# 05_UFS.net
KiCad netlist of a schematic drawn in Altium Designer
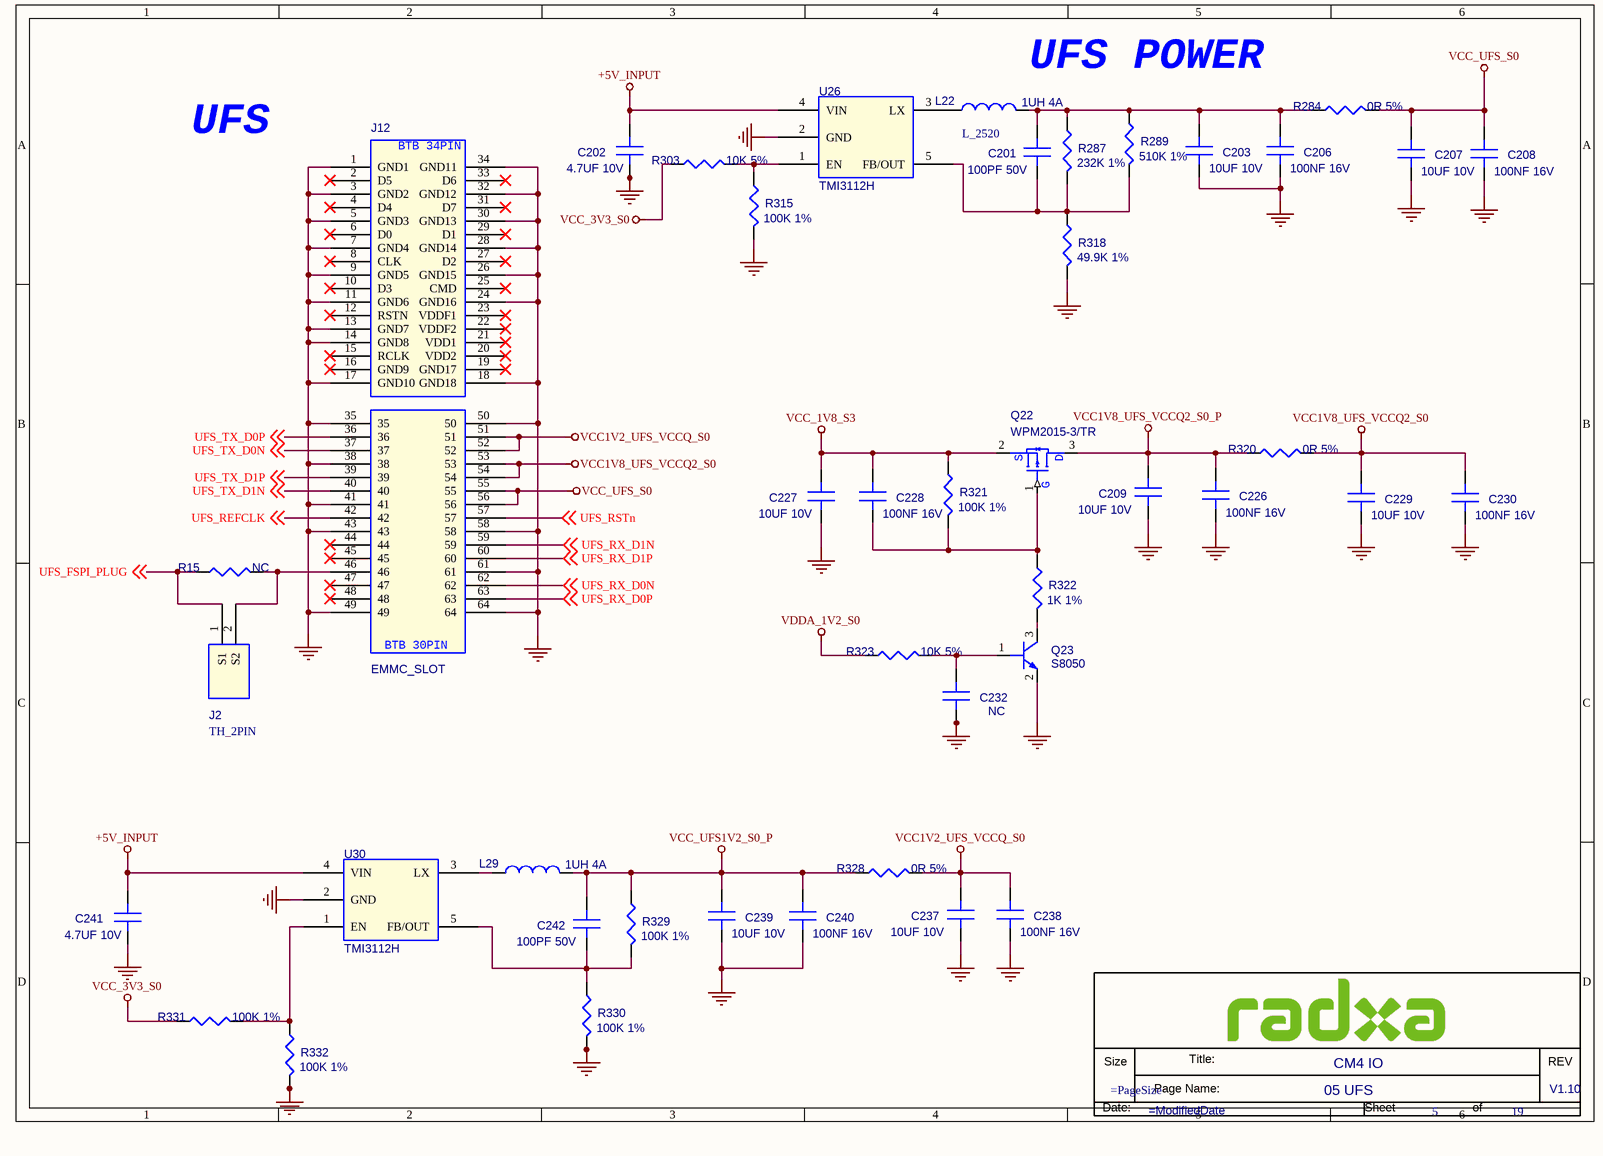
[diagram p0: 05 UFS.SchDoc]

(export (version "E")
  (design (tool "Eeschema 10.0.6"))
  (components
    (comp (ref "C201")
      (value "100PF 50V")
      (footprint "C0201")
      (description "SMD  0201  100PF  50V  X5R  ±5%  ROHS")
      (fields (field (name "PART NUMBER") "A1C01.00070"))
      (libsource (lib "*") (part "C"))
    )
    (comp (ref "C202")
      (value "4.7UF 10V")
      (footprint "C0402")
      (description "SMD  0402  4.7UF  10V  X5R  ±20%  ROHS")
      (fields (field (name "PART NUMBER") "A1C01.00073"))
      (libsource (lib "*") (part "C"))
    )
    (comp (ref "C203")
      (value "10UF 10V")
      (footprint "C0402")
      (description "SMD  0402  10UF  10V  X5R  ±20%  ROHS")
      (fields (field (name "PART NUMBER") "A1C01.00025"))
      (libsource (lib "*") (part "C"))
    )
    (comp (ref "C206")
      (value "100NF 16V")
      (footprint "C0201")
      (description "SMD  0201  100NF  16V  X5R  ±20%  ROHS")
      (fields (field (name "PART NUMBER") "A1C01.00099"))
      (libsource (lib "*") (part "C"))
    )
    (comp (ref "C207")
      (value "10UF 10V")
      (footprint "C0402")
      (description "SMD  0402  10UF  10V  X5R  ±20%  ROHS")
      (fields (field (name "PART NUMBER") "A1C01.00025"))
      (libsource (lib "*") (part "C"))
    )
    (comp (ref "C208")
      (value "100NF 16V")
      (footprint "C0201")
      (description "SMD  0201  100NF  16V  X5R  ±20%  ROHS")
      (fields (field (name "PART NUMBER") "A1C01.00099"))
      (libsource (lib "*") (part "C"))
    )
    (comp (ref "C209")
      (value "10UF 10V")
      (footprint "C0402")
      (description "SMD  0402  10UF  10V  X5R  ±20%  ROHS")
      (fields (field (name "PART NUMBER") "A1C01.00025"))
      (libsource (lib "*") (part "C"))
    )
    (comp (ref "C226")
      (value "100NF 16V")
      (footprint "C0201")
      (description "SMD  0201  100NF  16V  X5R  ±20%  ROHS")
      (fields (field (name "PART NUMBER") "A1C01.00099"))
      (libsource (lib "*") (part "C"))
    )
    (comp (ref "C227")
      (value "10UF 10V")
      (footprint "C0402")
      (description "SMD  0402  10UF  10V  X5R  ±20%  ROHS")
      (fields (field (name "PART NUMBER") "A1C01.00025"))
      (libsource (lib "*") (part "C"))
    )
    (comp (ref "C228")
      (value "100NF 16V")
      (footprint "C0201")
      (description "SMD  0201  100NF  16V  X5R  ±20%  ROHS")
      (fields (field (name "PART NUMBER") "A1C01.00099"))
      (libsource (lib "*") (part "C"))
    )
    (comp (ref "C229")
      (value "10UF 10V")
      (footprint "C0402")
      (description "SMD  0402  10UF  10V  X5R  ±20%  ROHS")
      (fields (field (name "PART NUMBER") "A1C01.00025"))
      (libsource (lib "*") (part "C"))
    )
    (comp (ref "C230")
      (value "100NF 16V")
      (footprint "C0201")
      (description "SMD  0201  100NF  16V  X5R  ±20%  ROHS")
      (fields (field (name "PART NUMBER") "A1C01.00099"))
      (libsource (lib "*") (part "C"))
    )
    (comp (ref "C232")
      (value "NC")
      (footprint "C0201")
      (description "SMD  0201  100NF  10V  X5R  ±20%  ROHS")
      (fields (field (name "PART NUMBER") "A1C01.00009"))
      (libsource (lib "*") (part "C"))
    )
    (comp (ref "C237")
      (value "10UF 10V")
      (footprint "C0402")
      (description "SMD  0402  10UF  10V  X5R  ±20%  ROHS")
      (fields (field (name "PART NUMBER") "A1C01.00025"))
      (libsource (lib "*") (part "C"))
    )
    (comp (ref "C238")
      (value "100NF 16V")
      (footprint "C0201")
      (description "SMD  0201  100NF  16V  X5R  ±20%  ROHS")
      (fields (field (name "PART NUMBER") "A1C01.00099"))
      (libsource (lib "*") (part "C"))
    )
    (comp (ref "C239")
      (value "10UF 10V")
      (footprint "C0402")
      (description "SMD  0402  10UF  10V  X5R  ±20%  ROHS")
      (fields (field (name "PART NUMBER") "A1C01.00025"))
      (libsource (lib "*") (part "C"))
    )
    (comp (ref "C240")
      (value "100NF 16V")
      (footprint "C0201")
      (description "SMD  0201  100NF  16V  X5R  ±20%  ROHS")
      (fields (field (name "PART NUMBER") "A1C01.00099"))
      (libsource (lib "*") (part "C"))
    )
    (comp (ref "C241")
      (value "4.7UF 10V")
      (footprint "C0402")
      (description "SMD  0402  4.7UF  10V  X5R  ±20%  ROHS")
      (fields (field (name "PART NUMBER") "A1C01.00073"))
      (libsource (lib "*") (part "C"))
    )
    (comp (ref "C242")
      (value "100PF 50V")
      (footprint "C0201")
      (description "SMD  0201  100PF  50V  X5R  ±5%  ROHS")
      (fields (field (name "PART NUMBER") "A1C01.00070"))
      (libsource (lib "*") (part "C"))
    )
    (comp (ref "J2")
      (value "TH_2PIN")
      (footprint "CON_TH1X2_2D54_STA")
      (fields (field (name "PART NUMBER") "A1J02.00011"))
      (libsource (lib "*") (part "TH_2PIN"))
    )
    (comp (ref "J12")
      (value "EMMC_SLOT")
      (footprint "EMMC_SLOT_30P_34P")
      (description "SMD  公座  2*17PIN  180度  8.3*2.7  0.4mm脚距  GB042-34P-H10-E3000  黑色  LG  ROHS")
      (fields (field (name "PART NUMBER") "A1J01.00030"))
      (libsource (lib "*") (part "EMMC_SLOT"))
    )
    (comp (ref "L22")
      (value "1UH 4A")
      (footprint "L_2520")
      (description "SMD  带屏蔽  2.5x2x1.2mm  1UH  4A  ±20%  RHP252012T-1R0MT  仁芯微  ROHS")
      (fields (field (name "PCB FOOTPRINT") "L_2520") (field (name "PART NUMBER") "A1L01.00117"))
      (libsource (lib "*") (part "L"))
    )
    (comp (ref "L29")
      (value "1UH 4A")
      (footprint "L_2520")
      (description "SMD  带屏蔽  2.5x2x1.2mm  1UH  4A  ±20%  RHP252012T-1R0MT  仁芯微  ROHS")
      (fields (field (name "PART NUMBER") "A1L01.00117"))
      (libsource (lib "*") (part "L"))
    )
    (comp (ref "Q22")
      (value "WPM2015-3/TR")
      (footprint "SOT_23")
      (description "SMD编带  SOT-23  WPM2015-3/TR  P沟道  ROHS")
      (fields (field (name "PART NUMBER") "A1D01.00019"))
      (libsource (lib "*") (part "MOSFET_PNP"))
    )
    (comp (ref "Q23")
      (value "S8050")
      (footprint "SOT_23")
      (description "SMD编带  SOT-23  S8050  NPN  ROHS")
      (fields
        (field (name "MANUFACTURER") "长电")
        (field (name "PART NUMBER") "A1D01.00009")
        (field (name "CREATED BY") "JJJ")
      )
      (libsource (lib "*") (part "NPN"))
    )
    (comp (ref "R15")
      (value "NC")
      (footprint "R0402")
      (description "SMD  0201  0R  1/20W  ±5%  ROHS")
      (fields (field (name "PART NUMBER") "A1R01.00027"))
      (libsource (lib "*") (part "R"))
    )
    (comp (ref "R284")
      (value "0R 5%")
      (footprint "R0402")
      (description "SMD  0201  0R  1/20W  ±5%  ROHS")
      (fields (field (name "PART NUMBER") "A1R01.00027"))
      (libsource (lib "*") (part "R"))
    )
    (comp (ref "R287")
      (value "232K 1%")
      (footprint "R0402")
      (description "SMD  0201  232K  1/20W  ±1%  ROHS")
      (fields (field (name "PART NUMBER") "A1R01.00189"))
      (libsource (lib "*") (part "R"))
    )
    (comp (ref "R289")
      (value "510K 1%")
      (footprint "R0402")
      (description "SMD  0201  510K  1/20W  ±1%  ROHS")
      (fields (field (name "PART NUMBER") "A1R01.00460"))
      (libsource (lib "*") (part "R"))
    )
    (comp (ref "R303")
      (value "10K 5%")
      (footprint "R0402")
      (description "SMD  0201  10K  1/20W  ±5%  ROHS")
      (fields (field (name "PART NUMBER") "A1R01.00012"))
      (libsource (lib "*") (part "R"))
    )
    (comp (ref "R315")
      (value "100K 1%")
      (footprint "R0402")
      (description "SMD  0201  100K  1/20W  ±1%  ROHS")
      (fields (field (name "PART NUMBER") "A1R01.00165"))
      (libsource (lib "*") (part "R"))
    )
    (comp (ref "R318")
      (value "49.9K 1%")
      (footprint "R0402")
      (description "SMD  0201  49.9K  1/20W  ±1%  ROHS")
      (fields (field (name "PART NUMBER") "A1R01.00207"))
      (libsource (lib "*") (part "R"))
    )
    (comp (ref "R320")
      (value "0R 5%")
      (footprint "R0402")
      (description "SMD  0201  0R  1/20W  ±5%  ROHS")
      (fields (field (name "PART NUMBER") "A1R01.00027"))
      (libsource (lib "*") (part "R"))
    )
    (comp (ref "R321")
      (value "100K 1%")
      (footprint "R0402")
      (description "SMD  0201  100K  1/20W  ±1%  ROHS")
      (fields (field (name "PART NUMBER") "A1R01.00165"))
      (libsource (lib "*") (part "R"))
    )
    (comp (ref "R322")
      (value "1K 1%")
      (footprint "R0402")
      (description "SMD  0201  1K  1/20W  ±1%  ROHS")
      (fields (field (name "PART NUMBER") "A1R01.00111"))
      (libsource (lib "*") (part "R"))
    )
    (comp (ref "R323")
      (value "10K 5%")
      (footprint "R0402")
      (description "SMD  0201  10K  1/20W  ±5%  ROHS")
      (fields (field (name "PART NUMBER") "A1R01.00012"))
      (libsource (lib "*") (part "R"))
    )
    (comp (ref "R328")
      (value "0R 5%")
      (footprint "R0402")
      (description "SMD  0201  0R  1/20W  ±5%  ROHS")
      (fields (field (name "PART NUMBER") "A1R01.00027"))
      (libsource (lib "*") (part "R"))
    )
    (comp (ref "R329")
      (value "100K 1%")
      (footprint "R0402")
      (description "SMD  0201  100K  1/20W  ±1%  ROHS")
      (fields (field (name "PART NUMBER") "A1R01.00165"))
      (libsource (lib "*") (part "R"))
    )
    (comp (ref "R330")
      (value "100K 1%")
      (footprint "R0402")
      (description "SMD  0201  100K  1/20W  ±1%  ROHS")
      (fields (field (name "PART NUMBER") "A1R01.00165"))
      (libsource (lib "*") (part "R"))
    )
    (comp (ref "R331")
      (value "100K 1%")
      (footprint "R0402")
      (description "SMD  0201  100K  1/20W  ±1%  ROHS")
      (fields (field (name "PART NUMBER") "A1R01.00165"))
      (libsource (lib "*") (part "R"))
    )
    (comp (ref "R332")
      (value "100K 1%")
      (footprint "R0402")
      (description "SMD  0201  100K  1/20W  ±1%  ROHS")
      (fields (field (name "PART NUMBER") "A1R01.00165"))
      (libsource (lib "*") (part "R"))
    )
    (comp (ref "U26")
      (value "TMI3112H")
      (footprint "SOT23_5")
      (description "SMD  降压转换器  TMI3112H  SOT-23-5  TMI  ROHS")
      (fields
        (field (name "PART NUMBER") "A1I01.00618")
        (field (name "MANUFACTURER") "TMI(拓尔微电子)")
        (field (name "CREATED BY") "JJJ")
      )
      (libsource (lib "*") (part "DCDC_ETA3409"))
    )
    (comp (ref "U30")
      (value "TMI3112H")
      (footprint "SOT23_5")
      (description "SMD  降压转换器  TMI3112H  SOT-23-5  TMI  ROHS")
      (fields
        (field (name "MANUFACTURER") "TMI(拓尔微电子)")
        (field (name "PART NUMBER") "A1I01.00618")
        (field (name "CREATED BY") "JJJ")
      )
      (libsource (lib "*") (part "DCDC_ETA3409"))
    )
  )
  (nets
    (net (code "1") (name "+5V_INPUT") (class "Default")
      (node (ref "C202") (pin "1") (pinfunction "A_1") (pintype "passive"))
      (node (ref "C241") (pin "1") (pinfunction "A_1") (pintype "passive"))
      (node (ref "U26") (pin "4") (pinfunction "VIN_4") (pintype "passive"))
      (node (ref "U30") (pin "4") (pinfunction "VIN_4") (pintype "passive"))
    )
    (net (code "2") (name "GND") (class "Default")
      (node (ref "C202") (pin "2") (pinfunction "B_2") (pintype "passive"))
      (node (ref "C203") (pin "2") (pinfunction "B_2") (pintype "passive"))
      (node (ref "C206") (pin "2") (pinfunction "B_2") (pintype "passive"))
      (node (ref "C207") (pin "2") (pinfunction "B_2") (pintype "passive"))
      (node (ref "C208") (pin "2") (pinfunction "B_2") (pintype "passive"))
      (node (ref "C209") (pin "2") (pinfunction "B_2") (pintype "passive"))
      (node (ref "C226") (pin "2") (pinfunction "B_2") (pintype "passive"))
      (node (ref "C227") (pin "2") (pinfunction "B_2") (pintype "passive"))
      (node (ref "C229") (pin "2") (pinfunction "B_2") (pintype "passive"))
      (node (ref "C230") (pin "2") (pinfunction "B_2") (pintype "passive"))
      (node (ref "C232") (pin "2") (pinfunction "B_2") (pintype "passive"))
      (node (ref "C237") (pin "2") (pinfunction "B_2") (pintype "passive"))
      (node (ref "C238") (pin "2") (pinfunction "B_2") (pintype "passive"))
      (node (ref "C239") (pin "2") (pinfunction "B_2") (pintype "passive"))
      (node (ref "C240") (pin "2") (pinfunction "B_2") (pintype "passive"))
      (node (ref "C241") (pin "2") (pinfunction "B_2") (pintype "passive"))
      (node (ref "J12") (pin "1") (pinfunction "GND1_1") (pintype "passive"))
      (node (ref "J12") (pin "11") (pinfunction "GND6_11") (pintype "passive"))
      (node (ref "J12") (pin "13") (pinfunction "GND7_13") (pintype "passive"))
      (node (ref "J12") (pin "14") (pinfunction "GND8_14") (pintype "passive"))
      (node (ref "J12") (pin "17") (pinfunction "GND10_17") (pintype "passive"))
      (node (ref "J12") (pin "18") (pinfunction "GND18_18") (pintype "passive"))
      (node (ref "J12") (pin "24") (pinfunction "GND16_24") (pintype "passive"))
      (node (ref "J12") (pin "26") (pinfunction "GND15_26") (pintype "passive"))
      (node (ref "J12") (pin "28") (pinfunction "GND14_28") (pintype "passive"))
      (node (ref "J12") (pin "3") (pinfunction "GND2_3") (pintype "passive"))
      (node (ref "J12") (pin "30") (pinfunction "GND13_30") (pintype "passive"))
      (node (ref "J12") (pin "32") (pinfunction "GND12_32") (pintype "passive"))
      (node (ref "J12") (pin "34") (pinfunction "GND11_34") (pintype "passive"))
      (node (ref "J12") (pin "35") (pinfunction "35_35") (pintype "passive"))
      (node (ref "J12") (pin "38") (pinfunction "38_38") (pintype "passive"))
      (node (ref "J12") (pin "41") (pinfunction "41_41") (pintype "passive"))
      (node (ref "J12") (pin "43") (pinfunction "43_43") (pintype "passive"))
      (node (ref "J12") (pin "49") (pinfunction "49_49") (pintype "passive"))
      (node (ref "J12") (pin "5") (pinfunction "GND3_5") (pintype "passive"))
      (node (ref "J12") (pin "50") (pinfunction "50_50") (pintype "passive"))
      (node (ref "J12") (pin "58") (pinfunction "58_58") (pintype "passive"))
      (node (ref "J12") (pin "61") (pinfunction "61_61") (pintype "passive"))
      (node (ref "J12") (pin "64") (pinfunction "64_64") (pintype "passive"))
      (node (ref "J12") (pin "7") (pinfunction "GND4_7") (pintype "passive"))
      (node (ref "J12") (pin "9") (pinfunction "GND5_9") (pintype "passive"))
      (node (ref "Q23") (pin "2") (pinfunction "EMITTER_2") (pintype "passive"))
      (node (ref "R315") (pin "2") (pinfunction "2_2") (pintype "passive"))
      (node (ref "R318") (pin "2") (pinfunction "2_2") (pintype "passive"))
      (node (ref "R330") (pin "2") (pinfunction "2_2") (pintype "passive"))
      (node (ref "R332") (pin "2") (pinfunction "2_2") (pintype "passive"))
      (node (ref "U26") (pin "2") (pinfunction "GND_2") (pintype "passive"))
      (node (ref "U30") (pin "2") (pinfunction "GND_2") (pintype "passive"))
    )
    (net (code "3") (name "Net-(C201-A)") (class "Default")
      (node (ref "C201") (pin "1") (pinfunction "A_1") (pintype "passive"))
      (node (ref "C203") (pin "1") (pinfunction "A_1") (pintype "passive"))
      (node (ref "C206") (pin "1") (pinfunction "A_1") (pintype "passive"))
      (node (ref "L22") (pin "2") (pinfunction "2_2") (pintype "passive"))
      (node (ref "R284") (pin "1") (pinfunction "1_1") (pintype "passive"))
      (node (ref "R287") (pin "1") (pinfunction "1_1") (pintype "passive"))
      (node (ref "R289") (pin "1") (pinfunction "1_1") (pintype "passive"))
    )
    (net (code "4") (name "Net-(C201-B)") (class "Default")
      (node (ref "C201") (pin "2") (pinfunction "B_2") (pintype "passive"))
      (node (ref "R287") (pin "2") (pinfunction "2_2") (pintype "passive"))
      (node (ref "R289") (pin "2") (pinfunction "2_2") (pintype "passive"))
      (node (ref "R318") (pin "1") (pinfunction "1_1") (pintype "passive"))
      (node (ref "U26") (pin "5") (pinfunction "FB/OUT_5") (pintype "passive"))
    )
    (net (code "5") (name "Net-(C228-B)") (class "Default")
      (node (ref "C228") (pin "2") (pinfunction "B_2") (pintype "passive"))
      (node (ref "Q22") (pin "1") (pinfunction "G_1") (pintype "input"))
      (node (ref "R321") (pin "2") (pinfunction "2_2") (pintype "passive"))
      (node (ref "R322") (pin "1") (pinfunction "1_1") (pintype "passive"))
    )
    (net (code "6") (name "Net-(C232-A)") (class "Default")
      (node (ref "C232") (pin "1") (pinfunction "A_1") (pintype "passive"))
      (node (ref "Q23") (pin "1") (pinfunction "BASE_1") (pintype "passive"))
      (node (ref "R323") (pin "2") (pinfunction "2_2") (pintype "passive"))
    )
    (net (code "7") (name "Net-(C242-B)") (class "Default")
      (node (ref "C242") (pin "2") (pinfunction "B_2") (pintype "passive"))
      (node (ref "R329") (pin "2") (pinfunction "2_2") (pintype "passive"))
      (node (ref "R330") (pin "1") (pinfunction "1_1") (pintype "passive"))
      (node (ref "U30") (pin "5") (pinfunction "FB/OUT_5") (pintype "passive"))
    )
    (net (code "8") (name "Net-(J2-S2)") (class "Default")
      (node (ref "J12") (pin "46") (pinfunction "46_46") (pintype "passive"))
      (node (ref "J2") (pin "2") (pinfunction "S2_2") (pintype "passive"))
      (node (ref "R15") (pin "2") (pinfunction "2_2") (pintype "passive"))
    )
    (net (code "9") (name "Net-(Q23-COLLECTOR)") (class "Default")
      (node (ref "Q23") (pin "3") (pinfunction "COLLECTOR_3") (pintype "passive"))
      (node (ref "R322") (pin "2") (pinfunction "2_2") (pintype "passive"))
    )
    (net (code "10") (name "Net-(U26-EN)") (class "Default")
      (node (ref "R303") (pin "2") (pinfunction "2_2") (pintype "passive"))
      (node (ref "R315") (pin "1") (pinfunction "1_1") (pintype "passive"))
      (node (ref "U26") (pin "1") (pinfunction "EN_1") (pintype "passive"))
    )
    (net (code "11") (name "Net-(U26-LX)") (class "Default")
      (node (ref "L22") (pin "1") (pinfunction "1_1") (pintype "passive"))
      (node (ref "U26") (pin "3") (pinfunction "LX_3") (pintype "passive"))
    )
    (net (code "12") (name "Net-(U30-EN)") (class "Default")
      (node (ref "R331") (pin "2") (pinfunction "2_2") (pintype "passive"))
      (node (ref "R332") (pin "1") (pinfunction "1_1") (pintype "passive"))
      (node (ref "U30") (pin "1") (pinfunction "EN_1") (pintype "passive"))
    )
    (net (code "13") (name "Net-(U30-LX)") (class "Default")
      (node (ref "L29") (pin "1") (pinfunction "1_1") (pintype "passive"))
      (node (ref "U30") (pin "3") (pinfunction "LX_3") (pintype "passive"))
    )
    (net (code "14") (name "UFS_FSPI_PLUG") (class "Default")
      (node (ref "J2") (pin "1") (pinfunction "S1_1") (pintype "passive"))
      (node (ref "R15") (pin "1") (pinfunction "1_1") (pintype "passive"))
    )
    (net (code "15") (name "UFS_REFCLK") (class "Default")
      (node (ref "J12") (pin "42") (pinfunction "42_42") (pintype "passive"))
    )
    (net (code "16") (name "UFS_RSTn") (class "Default")
      (node (ref "J12") (pin "57") (pinfunction "57_57") (pintype "passive"))
    )
    (net (code "17") (name "UFS_RX_D0N") (class "Default")
      (node (ref "J12") (pin "62") (pinfunction "62_62") (pintype "passive"))
    )
    (net (code "18") (name "UFS_RX_D0P") (class "Default")
      (node (ref "J12") (pin "63") (pinfunction "63_63") (pintype "passive"))
    )
    (net (code "19") (name "UFS_RX_D1N") (class "Default")
      (node (ref "J12") (pin "59") (pinfunction "59_59") (pintype "passive"))
    )
    (net (code "20") (name "UFS_RX_D1P") (class "Default")
      (node (ref "J12") (pin "60") (pinfunction "60_60") (pintype "passive"))
    )
    (net (code "21") (name "UFS_TX_D0N") (class "Default")
      (node (ref "J12") (pin "37") (pinfunction "37_37") (pintype "passive"))
    )
    (net (code "22") (name "UFS_TX_D0P") (class "Default")
      (node (ref "J12") (pin "36") (pinfunction "36_36") (pintype "passive"))
    )
    (net (code "23") (name "UFS_TX_D1N") (class "Default")
      (node (ref "J12") (pin "40") (pinfunction "40_40") (pintype "passive"))
    )
    (net (code "24") (name "UFS_TX_D1P") (class "Default")
      (node (ref "J12") (pin "39") (pinfunction "39_39") (pintype "passive"))
    )
    (net (code "25") (name "VCC1V2_UFS_VCCQ_S0") (class "Default")
      (node (ref "C237") (pin "1") (pinfunction "A_1") (pintype "passive"))
      (node (ref "C238") (pin "1") (pinfunction "A_1") (pintype "passive"))
      (node (ref "J12") (pin "51") (pinfunction "51_51") (pintype "passive"))
      (node (ref "J12") (pin "52") (pinfunction "52_52") (pintype "passive"))
      (node (ref "R328") (pin "2") (pinfunction "2_2") (pintype "passive"))
    )
    (net (code "26") (name "VCC1V8_UFS_VCCQ2_S0") (class "Default")
      (node (ref "C229") (pin "1") (pinfunction "A_1") (pintype "passive"))
      (node (ref "C230") (pin "1") (pinfunction "A_1") (pintype "passive"))
      (node (ref "J12") (pin "53") (pinfunction "53_53") (pintype "passive"))
      (node (ref "J12") (pin "54") (pinfunction "54_54") (pintype "passive"))
      (node (ref "R320") (pin "2") (pinfunction "2_2") (pintype "passive"))
    )
    (net (code "27") (name "VCC1V8_UFS_VCCQ2_S0_P") (class "Default")
      (node (ref "C209") (pin "1") (pinfunction "A_1") (pintype "passive"))
      (node (ref "C226") (pin "1") (pinfunction "A_1") (pintype "passive"))
      (node (ref "Q22") (pin "3") (pinfunction "D_3") (pintype "passive"))
      (node (ref "R320") (pin "1") (pinfunction "1_1") (pintype "passive"))
    )
    (net (code "28") (name "VCC_1V8_S3") (class "Default")
      (node (ref "C227") (pin "1") (pinfunction "A_1") (pintype "passive"))
      (node (ref "C228") (pin "1") (pinfunction "A_1") (pintype "passive"))
      (node (ref "Q22") (pin "2") (pinfunction "S_2") (pintype "passive"))
      (node (ref "R321") (pin "1") (pinfunction "1_1") (pintype "passive"))
    )
    (net (code "29") (name "VCC_3V3_S0") (class "Default")
      (node (ref "R303") (pin "1") (pinfunction "1_1") (pintype "passive"))
      (node (ref "R331") (pin "1") (pinfunction "1_1") (pintype "passive"))
    )
    (net (code "30") (name "VCC_UFS1V2_S0_P") (class "Default")
      (node (ref "C239") (pin "1") (pinfunction "A_1") (pintype "passive"))
      (node (ref "C240") (pin "1") (pinfunction "A_1") (pintype "passive"))
      (node (ref "C242") (pin "1") (pinfunction "A_1") (pintype "passive"))
      (node (ref "L29") (pin "2") (pinfunction "2_2") (pintype "passive"))
      (node (ref "R328") (pin "1") (pinfunction "1_1") (pintype "passive"))
      (node (ref "R329") (pin "1") (pinfunction "1_1") (pintype "passive"))
    )
    (net (code "31") (name "VCC_UFS_S0") (class "Default")
      (node (ref "C207") (pin "1") (pinfunction "A_1") (pintype "passive"))
      (node (ref "C208") (pin "1") (pinfunction "A_1") (pintype "passive"))
      (node (ref "J12") (pin "55") (pinfunction "55_55") (pintype "passive"))
      (node (ref "J12") (pin "56") (pinfunction "56_56") (pintype "passive"))
      (node (ref "R284") (pin "2") (pinfunction "2_2") (pintype "passive"))
    )
    (net (code "32") (name "VDDA_1V2_S0") (class "Default")
      (node (ref "R323") (pin "1") (pinfunction "1_1") (pintype "passive"))
    )
    (net (code "33") (name "unconnected-(J12-CLK-Pad8)") (class "Default")
      (node (ref "J12") (pin "8") (pinfunction "CLK_8") (pintype "passive+no_connect"))
    )
    (net (code "34") (name "unconnected-(J12-CMD-Pad25)") (class "Default")
      (node (ref "J12") (pin "25") (pinfunction "CMD_25") (pintype "passive+no_connect"))
    )
    (net (code "35") (name "unconnected-(J12-D0-Pad6)") (class "Default")
      (node (ref "J12") (pin "6") (pinfunction "D0_6") (pintype "passive+no_connect"))
    )
    (net (code "36") (name "unconnected-(J12-D1-Pad29)") (class "Default")
      (node (ref "J12") (pin "29") (pinfunction "D1_29") (pintype "passive+no_connect"))
    )
    (net (code "37") (name "unconnected-(J12-D2-Pad27)") (class "Default")
      (node (ref "J12") (pin "27") (pinfunction "D2_27") (pintype "passive+no_connect"))
    )
    (net (code "38") (name "unconnected-(J12-D3-Pad10)") (class "Default")
      (node (ref "J12") (pin "10") (pinfunction "D3_10") (pintype "passive+no_connect"))
    )
    (net (code "39") (name "unconnected-(J12-D4-Pad4)") (class "Default")
      (node (ref "J12") (pin "4") (pinfunction "D4_4") (pintype "passive+no_connect"))
    )
    (net (code "40") (name "unconnected-(J12-D5-Pad2)") (class "Default")
      (node (ref "J12") (pin "2") (pinfunction "D5_2") (pintype "passive+no_connect"))
    )
    (net (code "41") (name "unconnected-(J12-D6-Pad33)") (class "Default")
      (node (ref "J12") (pin "33") (pinfunction "D6_33") (pintype "passive+no_connect"))
    )
    (net (code "42") (name "unconnected-(J12-D7-Pad31)") (class "Default")
      (node (ref "J12") (pin "31") (pinfunction "D7_31") (pintype "passive+no_connect"))
    )
    (net (code "43") (name "unconnected-(J12-GND9-Pad16)") (class "Default")
      (node (ref "J12") (pin "16") (pinfunction "GND9_16") (pintype "passive+no_connect"))
    )
    (net (code "44") (name "unconnected-(J12-GND17-Pad19)") (class "Default")
      (node (ref "J12") (pin "19") (pinfunction "GND17_19") (pintype "passive+no_connect"))
    )
    (net (code "45") (name "unconnected-(J12-Pad44)") (class "Default")
      (node (ref "J12") (pin "44") (pinfunction "44_44") (pintype "passive+no_connect"))
    )
    (net (code "46") (name "unconnected-(J12-Pad45)") (class "Default")
      (node (ref "J12") (pin "45") (pinfunction "45_45") (pintype "passive+no_connect"))
    )
    (net (code "47") (name "unconnected-(J12-Pad47)") (class "Default")
      (node (ref "J12") (pin "47") (pinfunction "47_47") (pintype "passive+no_connect"))
    )
    (net (code "48") (name "unconnected-(J12-Pad48)") (class "Default")
      (node (ref "J12") (pin "48") (pinfunction "48_48") (pintype "passive+no_connect"))
    )
    (net (code "49") (name "unconnected-(J12-RCLK-Pad15)") (class "Default")
      (node (ref "J12") (pin "15") (pinfunction "RCLK_15") (pintype "passive+no_connect"))
    )
    (net (code "50") (name "unconnected-(J12-RSTN-Pad12)") (class "Default")
      (node (ref "J12") (pin "12") (pinfunction "RSTN_12") (pintype "passive+no_connect"))
    )
    (net (code "51") (name "unconnected-(J12-VDD1-Pad21)") (class "Default")
      (node (ref "J12") (pin "21") (pinfunction "VDD1_21") (pintype "passive+no_connect"))
    )
    (net (code "52") (name "unconnected-(J12-VDD2-Pad20)") (class "Default")
      (node (ref "J12") (pin "20") (pinfunction "VDD2_20") (pintype "passive+no_connect"))
    )
    (net (code "53") (name "unconnected-(J12-VDDF1-Pad23)") (class "Default")
      (node (ref "J12") (pin "23") (pinfunction "VDDF1_23") (pintype "passive+no_connect"))
    )
    (net (code "54") (name "unconnected-(J12-VDDF2-Pad22)") (class "Default")
      (node (ref "J12") (pin "22") (pinfunction "VDDF2_22") (pintype "passive+no_connect"))
    )
  )
)
